# e_BOOK_READER__VERSIUNE_10_v31_FIXED.net
KiCad netlist of a schematic drawn in EAGLE
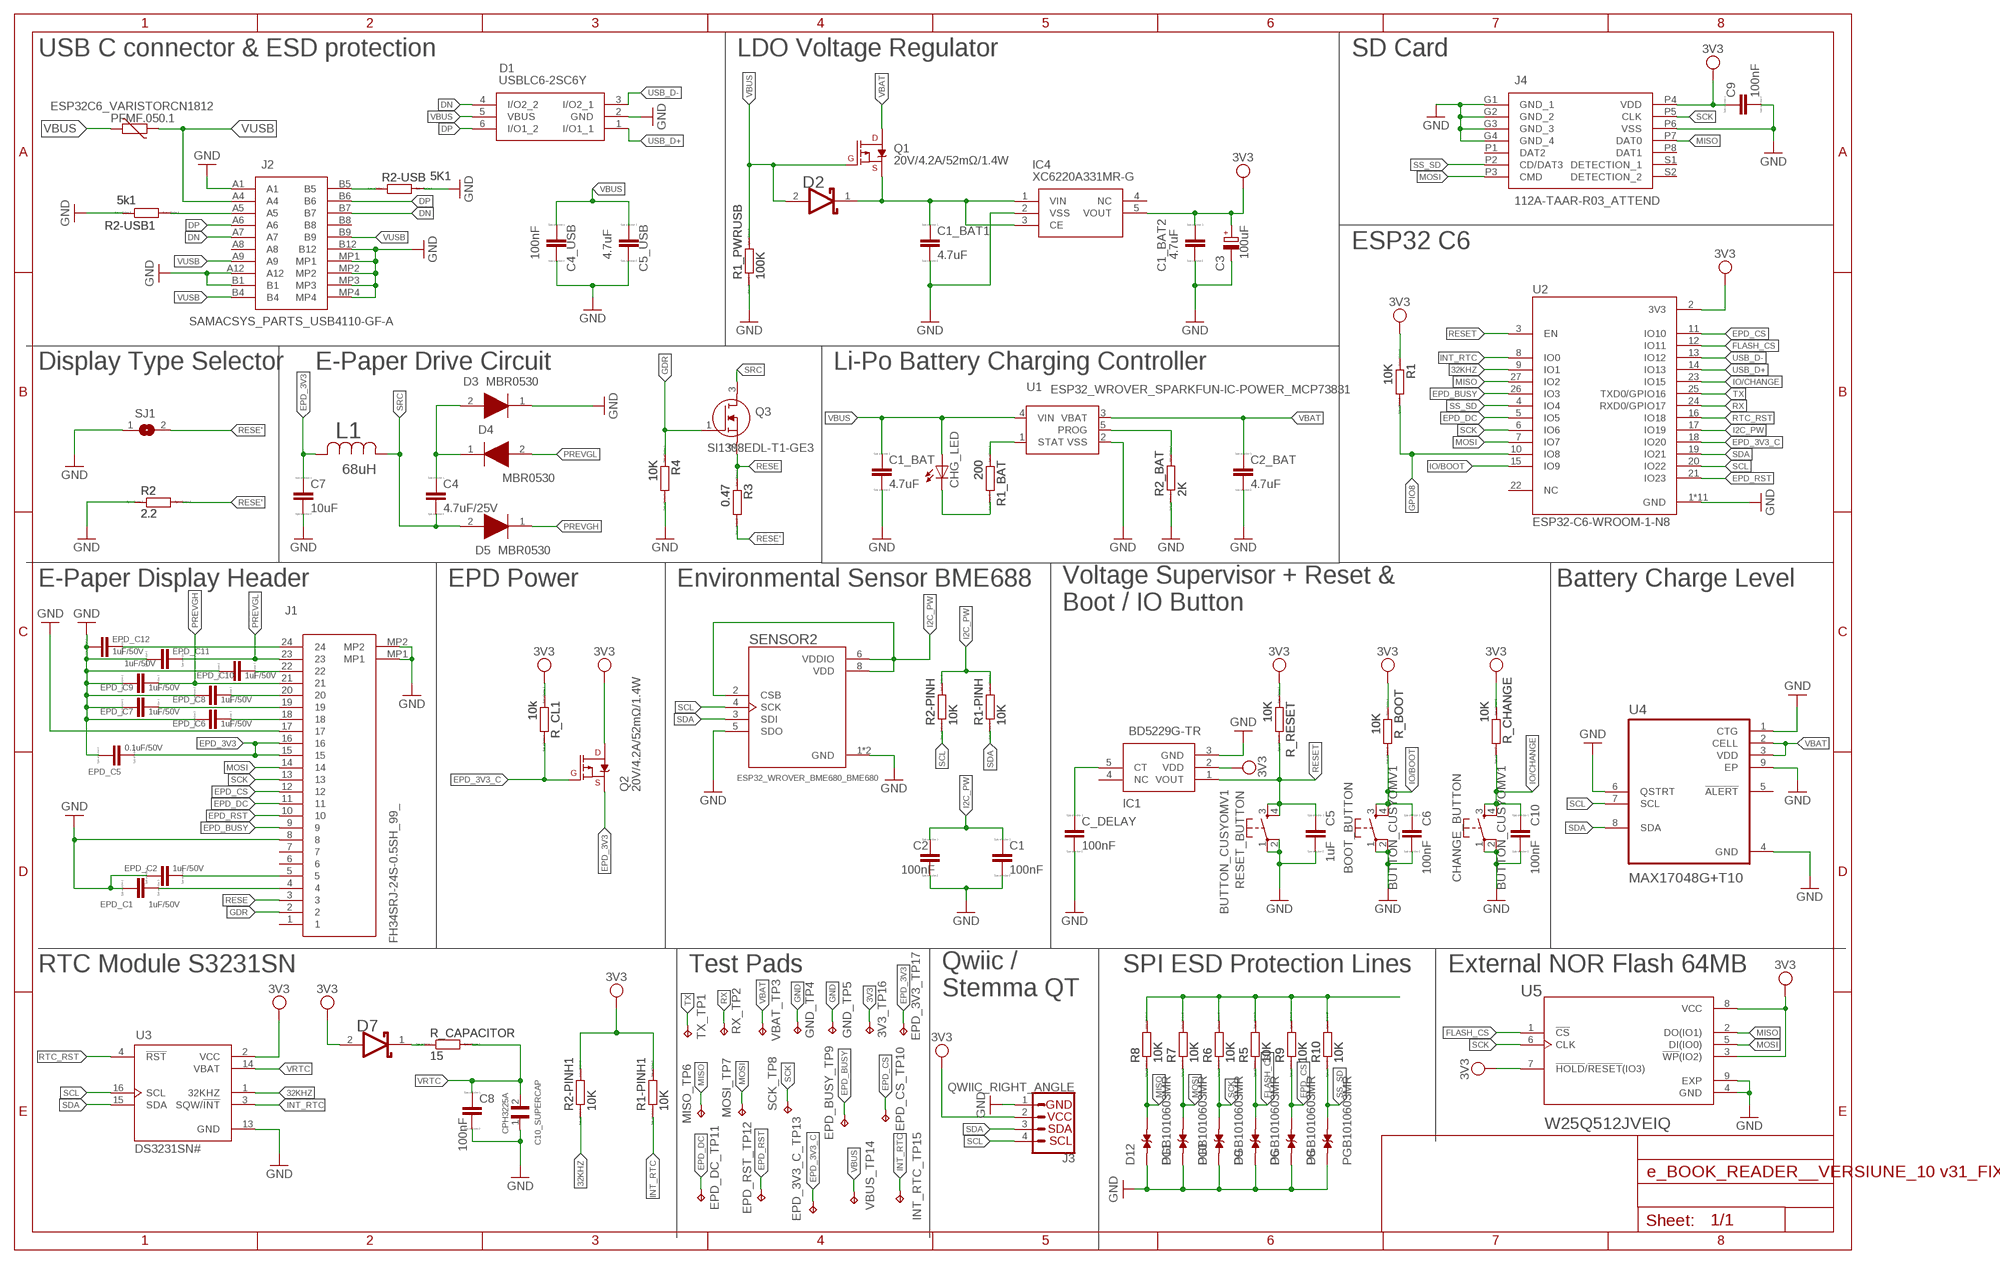
[diagram p0: schematic, sheet 1]

(export (version "E")
  (design (tool "Eeschema 10.0.6"))
  (components
    (comp (ref "3V3_TP16")
      (value "TPTP20R")
      (footprint "eagle-import:TP20R")
      (libsource (lib "eagle-import") (part "TPTP20R"))
    )
    (comp (ref "BOOT_BUTTON")
      (value "BUTTON_CUSYOMV1")
      (footprint "eagle-import:MYBUTTON")
      (libsource (lib "eagle-import") (part "BUTTON_CUSYOMV1"))
    )
    (comp (ref "C1")
      (value "100nF")
      (footprint "eagle-import:ESP32_WROVER_EAGLE-LTSPICE_C0402")
      (libsource (lib "eagle-import") (part "ESP32_WROVER_EAGLE-LTSPICE_CC0402"))
    )
    (comp (ref "C1_BAT")
      (value "4.7uF")
      (footprint "eagle-import:ESP32_WROVER_EAGLE-LTSPICE_C0402")
      (libsource (lib "eagle-import") (part "ESP32_WROVER_EAGLE-LTSPICE_CC0402"))
    )
    (comp (ref "C1_BAT1")
      (value "4.7uF")
      (footprint "eagle-import:ESP32_WROVER_EAGLE-LTSPICE_C0402")
      (libsource (lib "eagle-import") (part "ESP32_WROVER_EAGLE-LTSPICE_CC0402"))
    )
    (comp (ref "C1_BAT2")
      (value "4.7uF")
      (footprint "eagle-import:ESP32_WROVER_EAGLE-LTSPICE_C0402")
      (libsource (lib "eagle-import") (part "ESP32_WROVER_EAGLE-LTSPICE_CC0402"))
    )
    (comp (ref "C2")
      (value "100nF")
      (footprint "eagle-import:ESP32_WROVER_EAGLE-LTSPICE_C0402")
      (libsource (lib "eagle-import") (part "ESP32_WROVER_EAGLE-LTSPICE_CC0402"))
    )
    (comp (ref "C2_BAT")
      (value "4.7uF")
      (footprint "eagle-import:ESP32_WROVER_EAGLE-LTSPICE_C0402")
      (libsource (lib "eagle-import") (part "ESP32_WROVER_EAGLE-LTSPICE_CC0402"))
    )
    (comp (ref "C3")
      (value "100uF")
      (footprint "eagle-import:RCL_CT3528")
      (libsource (lib "eagle-import") (part "RCL_CPOL-EUCT3528"))
    )
    (comp (ref "C4")
      (value "4.7uF/25V")
      (footprint "eagle-import:ESP32_WROVER_EAGLE-LTSPICE_C0402")
      (libsource (lib "eagle-import") (part "ESP32_WROVER_EAGLE-LTSPICE_CC0402"))
    )
    (comp (ref "C4_USB")
      (value "100nF")
      (footprint "eagle-import:ESP32_WROVER_EAGLE-LTSPICE_C0402")
      (libsource (lib "eagle-import") (part "ESP32_WROVER_EAGLE-LTSPICE_CC0402"))
    )
    (comp (ref "C5")
      (value "1uF")
      (footprint "eagle-import:ESP32_WROVER_EAGLE-LTSPICE_C0402")
      (libsource (lib "eagle-import") (part "ESP32_WROVER_EAGLE-LTSPICE_CC0402"))
    )
    (comp (ref "C5_USB")
      (value "4.7uF")
      (footprint "eagle-import:ESP32_WROVER_EAGLE-LTSPICE_C0402")
      (libsource (lib "eagle-import") (part "ESP32_WROVER_EAGLE-LTSPICE_CC0402"))
    )
    (comp (ref "C6")
      (value "100nF")
      (footprint "eagle-import:ESP32_WROVER_EAGLE-LTSPICE_C0402")
      (libsource (lib "eagle-import") (part "ESP32_WROVER_EAGLE-LTSPICE_CC0402"))
    )
    (comp (ref "C7")
      (value "10uF")
      (footprint "eagle-import:ESP32_WROVER_EAGLE-LTSPICE_C0402")
      (libsource (lib "eagle-import") (part "ESP32_WROVER_EAGLE-LTSPICE_CC0402"))
    )
    (comp (ref "C8")
      (value "100nF")
      (footprint "eagle-import:ESP32_WROVER_EAGLE-LTSPICE_C0402")
      (libsource (lib "eagle-import") (part "ESP32_WROVER_EAGLE-LTSPICE_CC0402"))
    )
    (comp (ref "C9")
      (value "100nF")
      (footprint "eagle-import:ESP32_WROVER_EAGLE-LTSPICE_C0402")
      (libsource (lib "eagle-import") (part "ESP32_WROVER_EAGLE-LTSPICE_CC0402"))
    )
    (comp (ref "C10")
      (value "100nF")
      (footprint "eagle-import:ESP32_WROVER_EAGLE-LTSPICE_C0402")
      (libsource (lib "eagle-import") (part "ESP32_WROVER_EAGLE-LTSPICE_CC0402"))
    )
    (comp (ref "C10_SUPERCAP")
      (value "CPH3225A")
      (footprint "eagle-import:CAPCP3225X100N")
      (fields (field (name "MF") "Seiko Instruments"))
      (libsource (lib "eagle-import") (part "CPH3225A"))
    )
    (comp (ref "CHANGE_BUTTON")
      (value "BUTTON_CUSYOMV1")
      (footprint "eagle-import:MYBUTTON")
      (libsource (lib "eagle-import") (part "BUTTON_CUSYOMV1"))
    )
    (comp (ref "CHG_LED")
      (value "ADAFRUIT_LEDCHIP-LED0603")
      (footprint "eagle-import:ADAFRUIT_CHIP-LED0603")
      (libsource (lib "eagle-import") (part "ADAFRUIT_LEDCHIP-LED0603"))
    )
    (comp (ref "C_DELAY")
      (value "100nF")
      (footprint "eagle-import:ESP32_WROVER_EAGLE-LTSPICE_C0402")
      (libsource (lib "eagle-import") (part "ESP32_WROVER_EAGLE-LTSPICE_CC0402"))
    )
    (comp (ref "D1")
      (value "USBLC6-2SC6Y")
      (footprint "eagle-import:SOT95P280X145-6N")
      (fields (field (name "MF") "STMicroelectronics"))
      (libsource (lib "eagle-import") (part "USBLC6-2SC6Y"))
    )
    (comp (ref "D2")
      (value "ESP32_WROVER_AVX---SD0805S020S1R0_AVX_SD0805S020S1R0_0_0AVX_SD0805S020S1R0_0_0")
      (footprint "eagle-import:ESP32_WROVER_AVX---SD0805S020S1R0_AVX_SD0805S020S1R0_0")
      (fields
        (field (name "DIGIKEY_PART_NUMBER") "478-7800-1-ND")
        (field (name "MF") "AVX")
        (field (name "MOUSER_PART_NUMBER") "581-SD0805S020S1R0")
      )
      (libsource (lib "eagle-import") (part "ESP32_WROVER_AVX---SD0805S020S1R0_AVX_SD0805S020S1R0_0_0AVX_SD0805S020S1R0_0_0"))
    )
    (comp (ref "D3")
      (value "MBR0530")
      (footprint "eagle-import:ESP32_WROVER_AVX---SD0805S020S1R0_AVX_SD0805S020S1R0_0")
      (fields (field (name "MF") "ON Semiconductor"))
      (libsource (lib "eagle-import") (part "MBR0530"))
    )
    (comp (ref "D4")
      (value "MBR0530")
      (footprint "eagle-import:ESP32_WROVER_AVX---SD0805S020S1R0_AVX_SD0805S020S1R0_0")
      (fields (field (name "MF") "ON Semiconductor"))
      (libsource (lib "eagle-import") (part "MBR0530"))
    )
    (comp (ref "D5")
      (value "MBR0530")
      (footprint "eagle-import:ESP32_WROVER_AVX---SD0805S020S1R0_AVX_SD0805S020S1R0_0")
      (fields (field (name "MF") "ON Semiconductor"))
      (libsource (lib "eagle-import") (part "MBR0530"))
    )
    (comp (ref "D6")
      (value "PGB1010603MR")
      (footprint "eagle-import:DIOC1608X36N")
      (fields (field (name "MF") "Littelfuse Inc."))
      (libsource (lib "eagle-import") (part "PGB1010603MR"))
    )
    (comp (ref "D7")
      (value "ESP32_WROVER_AVX---SD0805S020S1R0_AVX_SD0805S020S1R0_0_0AVX_SD0805S020S1R0_0_0")
      (footprint "eagle-import:ESP32_WROVER_AVX---SD0805S020S1R0_AVX_SD0805S020S1R0_0")
      (fields
        (field (name "DIGIKEY_PART_NUMBER") "478-7800-1-ND")
        (field (name "MF") "AVX")
        (field (name "MOUSER_PART_NUMBER") "581-SD0805S020S1R0")
      )
      (libsource (lib "eagle-import") (part "ESP32_WROVER_AVX---SD0805S020S1R0_AVX_SD0805S020S1R0_0_0AVX_SD0805S020S1R0_0_0"))
    )
    (comp (ref "D8")
      (value "PGB1010603MR")
      (footprint "eagle-import:DIOC1608X36N")
      (fields (field (name "MF") "Littelfuse Inc."))
      (libsource (lib "eagle-import") (part "PGB1010603MR"))
    )
    (comp (ref "D9")
      (value "PGB1010603MR")
      (footprint "eagle-import:DIOC1608X36N")
      (fields (field (name "MF") "Littelfuse Inc."))
      (libsource (lib "eagle-import") (part "PGB1010603MR"))
    )
    (comp (ref "D10")
      (value "PGB1010603MR")
      (footprint "eagle-import:DIOC1608X36N")
      (fields (field (name "MF") "Littelfuse Inc."))
      (libsource (lib "eagle-import") (part "PGB1010603MR"))
    )
    (comp (ref "D11")
      (value "PGB1010603MR")
      (footprint "eagle-import:DIOC1608X36N")
      (fields (field (name "MF") "Littelfuse Inc."))
      (libsource (lib "eagle-import") (part "PGB1010603MR"))
    )
    (comp (ref "D12")
      (value "PGB1010603MR")
      (footprint "eagle-import:DIOC1608X36N")
      (fields (field (name "MF") "Littelfuse Inc."))
      (libsource (lib "eagle-import") (part "PGB1010603MR"))
    )
    (comp (ref "EPD_3V3_C_TP13")
      (value "TPTP20R")
      (footprint "eagle-import:TP20R")
      (libsource (lib "eagle-import") (part "TPTP20R"))
    )
    (comp (ref "EPD_3V3_TP17")
      (value "TPTP20R")
      (footprint "eagle-import:TP20R")
      (libsource (lib "eagle-import") (part "TPTP20R"))
    )
    (comp (ref "EPD_BUSY_TP9")
      (value "TPTP20R")
      (footprint "eagle-import:TP20R")
      (libsource (lib "eagle-import") (part "TPTP20R"))
    )
    (comp (ref "EPD_C1")
      (value "1uF/50V")
      (footprint "eagle-import:ESP32_WROVER_EAGLE-LTSPICE_C0402")
      (libsource (lib "eagle-import") (part "ESP32_WROVER_EAGLE-LTSPICE_CC0402"))
    )
    (comp (ref "EPD_C2")
      (value "1uF/50V")
      (footprint "eagle-import:ESP32_WROVER_EAGLE-LTSPICE_C0402")
      (libsource (lib "eagle-import") (part "ESP32_WROVER_EAGLE-LTSPICE_CC0402"))
    )
    (comp (ref "EPD_C5")
      (value "0.1uF/50V")
      (footprint "eagle-import:ESP32_WROVER_EAGLE-LTSPICE_C0402")
      (libsource (lib "eagle-import") (part "ESP32_WROVER_EAGLE-LTSPICE_CC0402"))
    )
    (comp (ref "EPD_C6")
      (value "1uF/50V")
      (footprint "eagle-import:ESP32_WROVER_EAGLE-LTSPICE_C0402")
      (libsource (lib "eagle-import") (part "ESP32_WROVER_EAGLE-LTSPICE_CC0402"))
    )
    (comp (ref "EPD_C7")
      (value "1uF/50V")
      (footprint "eagle-import:ESP32_WROVER_EAGLE-LTSPICE_C0402")
      (libsource (lib "eagle-import") (part "ESP32_WROVER_EAGLE-LTSPICE_CC0402"))
    )
    (comp (ref "EPD_C8")
      (value "1uF/50V")
      (footprint "eagle-import:ESP32_WROVER_EAGLE-LTSPICE_C0402")
      (libsource (lib "eagle-import") (part "ESP32_WROVER_EAGLE-LTSPICE_CC0402"))
    )
    (comp (ref "EPD_C9")
      (value "1uF/50V")
      (footprint "eagle-import:ESP32_WROVER_EAGLE-LTSPICE_C0402")
      (libsource (lib "eagle-import") (part "ESP32_WROVER_EAGLE-LTSPICE_CC0402"))
    )
    (comp (ref "EPD_C10")
      (value "1uF/50V")
      (footprint "eagle-import:ESP32_WROVER_EAGLE-LTSPICE_C0402")
      (libsource (lib "eagle-import") (part "ESP32_WROVER_EAGLE-LTSPICE_CC0402"))
    )
    (comp (ref "EPD_C11")
      (value "1uF/50V")
      (footprint "eagle-import:ESP32_WROVER_EAGLE-LTSPICE_C0402")
      (libsource (lib "eagle-import") (part "ESP32_WROVER_EAGLE-LTSPICE_CC0402"))
    )
    (comp (ref "EPD_C12")
      (value "1uF/50V")
      (footprint "eagle-import:ESP32_WROVER_EAGLE-LTSPICE_C0402")
      (libsource (lib "eagle-import") (part "ESP32_WROVER_EAGLE-LTSPICE_CC0402"))
    )
    (comp (ref "EPD_CS_TP10")
      (value "TPTP20R")
      (footprint "eagle-import:TP20R")
      (libsource (lib "eagle-import") (part "TPTP20R"))
    )
    (comp (ref "EPD_DC_TP11")
      (value "TPTP20R")
      (footprint "eagle-import:TP20R")
      (libsource (lib "eagle-import") (part "TPTP20R"))
    )
    (comp (ref "EPD_RST_TP12")
      (value "TPTP20R")
      (footprint "eagle-import:TP20R")
      (libsource (lib "eagle-import") (part "TPTP20R"))
    )
    (comp (ref "GND_TP4")
      (value "TPTP20R")
      (footprint "eagle-import:TP20R")
      (libsource (lib "eagle-import") (part "TPTP20R"))
    )
    (comp (ref "GND_TP5")
      (value "TPTP20R")
      (footprint "eagle-import:TP20R")
      (libsource (lib "eagle-import") (part "TPTP20R"))
    )
    (comp (ref "IC1")
      (value "BD5229G-TR")
      (footprint "eagle-import:SOT95P280X125-5N")
      (fields (field (name "MOUSER_PART_NUMBER") "755-BD5229G-TR"))
      (libsource (lib "eagle-import") (part "BD5229G-TR"))
    )
    (comp (ref "IC4")
      (value "XC6220A331MR-G")
      (footprint "eagle-import:SOT95P280X120-5N")
      (fields (field (name "MOUSER_PART_NUMBER") "865-XC6220A331MR-G"))
      (libsource (lib "eagle-import") (part "XC6220A331MR-G"))
    )
    (comp (ref "INT_RTC_TP15")
      (value "TPTP20R")
      (footprint "eagle-import:TP20R")
      (libsource (lib "eagle-import") (part "TPTP20R"))
    )
    (comp (ref "J1")
      (value "FH34SRJ-24S-0.5SH_99_")
      (footprint "eagle-import:FH34SRJ24S05SH99")
      (fields
        (field (name "MANUFACTURER_PART_NUMBER") "FH34SRJ-24S-0.5SH(99)")
        (field (name "MOUSER_PART_NUMBER") "798-FH34SRJ24S05SH99")
      )
      (libsource (lib "eagle-import") (part "FH34SRJ-24S-0.5SH_99_"))
    )
    (comp (ref "J2")
      (value "SAMACSYS_PARTS_USB4110-GF-A")
      (footprint "eagle-import:SAMACSYS_PARTS_USB4110GFA")
      (fields
        (field (name "MANUFACTURER_PART_NUMBER") "USB4110-GF-A")
        (field (name "MOUSER_PART_NUMBER") "640-USB4110-GF-A")
      )
      (libsource (lib "eagle-import") (part "SAMACSYS_PARTS_USB4110-GF-A"))
    )
    (comp (ref "J3")
      (value "QWIIC_RIGHT_ANGLE")
      (footprint "eagle-import:JST04_1MM_RA")
      (libsource (lib "eagle-import") (part "QWIIC_CONNECTORJS-1MM"))
    )
    (comp (ref "J4")
      (value "112A-TAAR-R03_ATTEND")
      (footprint "eagle-import:112ATAARR03ATTEND")
      (fields (field (name "MANUFACTURER_PART_NUMBER") "112A-TAAR-R03 ATTEND"))
      (libsource (lib "eagle-import") (part "112A-TAAR-R03_ATTEND"))
    )
    (comp (ref "L1")
      (value "68uH")
      (footprint "eagle-import:IND_4828-WE-TPC_WRE")
      (fields
        (field (name "MANUFACTURER_PART_NUMBER") "744043680")
        (field (name "COPYRIGHT") "Copyright (C) 2024 Ultra Librarian. All rights reserved.")
      )
      (libsource (lib "eagle-import") (part "744043680IND_4828-WE-TPC_WRE"))
    )
    (comp (ref "MISO_TP6")
      (value "TPTP20R")
      (footprint "eagle-import:TP20R")
      (libsource (lib "eagle-import") (part "TPTP20R"))
    )
    (comp (ref "MOSI_TP7")
      (value "TPTP20R")
      (footprint "eagle-import:TP20R")
      (libsource (lib "eagle-import") (part "TPTP20R"))
    )
    (comp (ref "PFMF.050.1")
      (value "ESP32C6_VARISTORCN1812")
      (footprint "eagle-import:ESP32C6_VARISTOR_CT_CN1812")
      (libsource (lib "eagle-import") (part "ESP32C6_VARISTORCN1812"))
    )
    (comp (ref "Q1")
      (value "20V/4.2A/52mΩ/1.4W")
      (footprint "eagle-import:ESP32_WROVER_SPARKFUN-DISCRETESEMI_SOT23-3")
      (libsource (lib "eagle-import") (part "ESP32_WROVER_SPARKFUN-DISCRETESEMI_MOSFET_PCH-DMG2305UX-7"))
    )
    (comp (ref "Q2")
      (value "20V/4.2A/52mΩ/1.4W")
      (footprint "eagle-import:ESP32_WROVER_SPARKFUN-DISCRETESEMI_SOT23-3")
      (libsource (lib "eagle-import") (part "ESP32_WROVER_SPARKFUN-DISCRETESEMI_MOSFET_PCH-DMG2305UX-7"))
    )
    (comp (ref "Q3")
      (value "SI1308EDL-T1-GE3")
      (footprint "eagle-import:SOT65P210X110-3N")
      (fields (field (name "MF") "Vishay Siliconix"))
      (libsource (lib "eagle-import") (part "SI1308EDL-T1-GE3"))
    )
    (comp (ref "R1")
      (value "10K")
      (footprint "eagle-import:ESP32_WROVER_EAGLE-LTSPICE_R0402")
      (libsource (lib "eagle-import") (part "ESP32_WROVER_EAGLE-LTSPICE_RR0402"))
    )
    (comp (ref "R1-PINH")
      (value "10K")
      (footprint "eagle-import:ESP32_WROVER_EAGLE-LTSPICE_R0402")
      (libsource (lib "eagle-import") (part "ESP32_WROVER_EAGLE-LTSPICE_RR0402"))
    )
    (comp (ref "R1-PINH1")
      (value "10K")
      (footprint "eagle-import:ESP32_WROVER_EAGLE-LTSPICE_R0402")
      (libsource (lib "eagle-import") (part "ESP32_WROVER_EAGLE-LTSPICE_RR0402"))
    )
    (comp (ref "R1_BAT")
      (value "200")
      (footprint "eagle-import:ESP32_WROVER_EAGLE-LTSPICE_R0402")
      (libsource (lib "eagle-import") (part "ESP32_WROVER_EAGLE-LTSPICE_RR0402"))
    )
    (comp (ref "R1_PWRUSB")
      (value "100K")
      (footprint "eagle-import:ESP32_WROVER_EAGLE-LTSPICE_R0402")
      (libsource (lib "eagle-import") (part "ESP32_WROVER_EAGLE-LTSPICE_RR0402"))
    )
    (comp (ref "R2")
      (value "2.2")
      (footprint "eagle-import:ESP32_WROVER_EAGLE-LTSPICE_R0402")
      (libsource (lib "eagle-import") (part "ESP32_WROVER_EAGLE-LTSPICE_RR0402"))
    )
    (comp (ref "R2-PINH")
      (value "10K")
      (footprint "eagle-import:ESP32_WROVER_EAGLE-LTSPICE_R0402")
      (libsource (lib "eagle-import") (part "ESP32_WROVER_EAGLE-LTSPICE_RR0402"))
    )
    (comp (ref "R2-PINH1")
      (value "10K")
      (footprint "eagle-import:ESP32_WROVER_EAGLE-LTSPICE_R0402")
      (libsource (lib "eagle-import") (part "ESP32_WROVER_EAGLE-LTSPICE_RR0402"))
    )
    (comp (ref "R2-USB")
      (value "5K1")
      (footprint "eagle-import:ESP32_WROVER_EAGLE-LTSPICE_R0402")
      (libsource (lib "eagle-import") (part "ESP32_WROVER_EAGLE-LTSPICE_RR0402"))
    )
    (comp (ref "R2-USB1")
      (value "5k1")
      (footprint "eagle-import:ESP32_WROVER_EAGLE-LTSPICE_R0402")
      (libsource (lib "eagle-import") (part "ESP32_WROVER_EAGLE-LTSPICE_RR0402"))
    )
    (comp (ref "R2_BAT")
      (value "2K")
      (footprint "eagle-import:ESP32_WROVER_EAGLE-LTSPICE_R0402")
      (libsource (lib "eagle-import") (part "ESP32_WROVER_EAGLE-LTSPICE_RR0402"))
    )
    (comp (ref "R3")
      (value "0.47")
      (footprint "eagle-import:ESP32_WROVER_EAGLE-LTSPICE_R0402")
      (libsource (lib "eagle-import") (part "ESP32_WROVER_EAGLE-LTSPICE_RR0402"))
    )
    (comp (ref "R4")
      (value "10K")
      (footprint "eagle-import:ESP32_WROVER_EAGLE-LTSPICE_R0402")
      (libsource (lib "eagle-import") (part "ESP32_WROVER_EAGLE-LTSPICE_RR0402"))
    )
    (comp (ref "R5")
      (value "10K")
      (footprint "eagle-import:ESP32_WROVER_EAGLE-LTSPICE_R0402")
      (libsource (lib "eagle-import") (part "ESP32_WROVER_EAGLE-LTSPICE_RR0402"))
    )
    (comp (ref "R6")
      (value "10K")
      (footprint "eagle-import:ESP32_WROVER_EAGLE-LTSPICE_R0402")
      (libsource (lib "eagle-import") (part "ESP32_WROVER_EAGLE-LTSPICE_RR0402"))
    )
    (comp (ref "R7")
      (value "10K")
      (footprint "eagle-import:ESP32_WROVER_EAGLE-LTSPICE_R0402")
      (libsource (lib "eagle-import") (part "ESP32_WROVER_EAGLE-LTSPICE_RR0402"))
    )
    (comp (ref "R8")
      (value "10K")
      (footprint "eagle-import:ESP32_WROVER_EAGLE-LTSPICE_R0402")
      (libsource (lib "eagle-import") (part "ESP32_WROVER_EAGLE-LTSPICE_RR0402"))
    )
    (comp (ref "R9")
      (value "10K")
      (footprint "eagle-import:ESP32_WROVER_EAGLE-LTSPICE_R0402")
      (libsource (lib "eagle-import") (part "ESP32_WROVER_EAGLE-LTSPICE_RR0402"))
    )
    (comp (ref "R10")
      (value "10K")
      (footprint "eagle-import:ESP32_WROVER_EAGLE-LTSPICE_R0402")
      (libsource (lib "eagle-import") (part "ESP32_WROVER_EAGLE-LTSPICE_RR0402"))
    )
    (comp (ref "RESET_BUTTON")
      (value "BUTTON_CUSYOMV1")
      (footprint "eagle-import:MYBUTTON")
      (libsource (lib "eagle-import") (part "BUTTON_CUSYOMV1"))
    )
    (comp (ref "RX_TP2")
      (value "TPTP20R")
      (footprint "eagle-import:TP20R")
      (libsource (lib "eagle-import") (part "TPTP20R"))
    )
    (comp (ref "R_BOOT")
      (value "10K")
      (footprint "eagle-import:ESP32_WROVER_EAGLE-LTSPICE_R0402")
      (libsource (lib "eagle-import") (part "ESP32_WROVER_EAGLE-LTSPICE_RR0402"))
    )
    (comp (ref "R_CAPACITOR")
      (value "15")
      (footprint "eagle-import:ESP32_WROVER_EAGLE-LTSPICE_R0402")
      (libsource (lib "eagle-import") (part "ESP32_WROVER_EAGLE-LTSPICE_RR0402"))
    )
    (comp (ref "R_CHANGE")
      (value "10K")
      (footprint "eagle-import:ESP32_WROVER_EAGLE-LTSPICE_R0402")
      (libsource (lib "eagle-import") (part "ESP32_WROVER_EAGLE-LTSPICE_RR0402"))
    )
    (comp (ref "R_CL1")
      (value "10k")
      (footprint "eagle-import:ESP32_WROVER_EAGLE-LTSPICE_R0402")
      (libsource (lib "eagle-import") (part "ESP32_WROVER_EAGLE-LTSPICE_RR0402"))
    )
    (comp (ref "R_RESET")
      (value "10K")
      (footprint "eagle-import:ESP32_WROVER_EAGLE-LTSPICE_R0402")
      (libsource (lib "eagle-import") (part "ESP32_WROVER_EAGLE-LTSPICE_RR0402"))
    )
    (comp (ref "SCK_TP8")
      (value "TPTP20R")
      (footprint "eagle-import:TP20R")
      (libsource (lib "eagle-import") (part "TPTP20R"))
    )
    (comp (ref "SENSOR2")
      (value "ESP32_WROVER_BME680_BME680")
      (footprint "eagle-import:ESP32_WROVER_BME680_PSON80P300X300X100-8N")
      (fields (field (name "MF") "Bosch Sensortec") (field (name "MP") "BME680"))
      (libsource (lib "eagle-import") (part "ESP32_WROVER_BME680_BME680"))
    )
    (comp (ref "SJ1") (value "SJ") (footprint "eagle-import:SJ") (libsource (lib "eagle-import") (part "SJ")))
    (comp (ref "TX_TP1")
      (value "TPTP20R")
      (footprint "eagle-import:TP20R")
      (libsource (lib "eagle-import") (part "TPTP20R"))
    )
    (comp (ref "U1")
      (value "ESP32_WROVER_SPARKFUN-IC-POWER_MCP73831")
      (footprint "eagle-import:ESP32_WROVER_SPARKFUN-IC-POWER_SOT23-5")
      (libsource (lib "eagle-import") (part "ESP32_WROVER_SPARKFUN-IC-POWER_MCP73831"))
    )
    (comp (ref "U2")
      (value "ESP32-C6-WROOM-1-N8")
      (footprint "eagle-import:XCVR_ESP32-C6-WROOM-1-N8")
      (fields (field (name "MF") "Espressif Systems"))
      (libsource (lib "eagle-import") (part "ESP32-C6-WROOM-1-N8"))
    )
    (comp (ref "U3")
      (value "DS3231SN#")
      (footprint "eagle-import:SOIC127P1032X265-16N")
      (fields (field (name "MF") "Analog Devices"))
      (libsource (lib "eagle-import") (part "DS3231SN#"))
    )
    (comp (ref "U4")
      (value "MAX17048G+T10")
      (footprint "eagle-import:SON50P200X200X80-9N")
      (fields (field (name "MF") "Analog Devices"))
      (libsource (lib "eagle-import") (part "MAX17048G+T10"))
    )
    (comp (ref "U5")
      (value "W25Q512JVEIQ")
      (footprint "eagle-import:SON127P600X800X80-9N")
      (fields (field (name "MF") "Winbond Electronics"))
      (libsource (lib "eagle-import") (part "W25Q512JVEIQ"))
    )
    (comp (ref "VBAT_TP3")
      (value "TPTP20R")
      (footprint "eagle-import:TP20R")
      (libsource (lib "eagle-import") (part "TPTP20R"))
    )
    (comp (ref "VBUS_TP14")
      (value "TPTP20R")
      (footprint "eagle-import:TP20R")
      (libsource (lib "eagle-import") (part "TPTP20R"))
    )
  )
  (nets
    (net (code "1") (name "3V3") (class "Default")
      (node (ref "3V3_TP16") (pin "TP") (pinfunction "TP_TP") (pintype "input"))
      (node (ref "C1_BAT2") (pin "1") (pinfunction "1_1") (pintype "passive"))
      (node (ref "C3") (pin "+") (pinfunction "+_+") (pintype "passive"))
      (node (ref "C9") (pin "1") (pinfunction "1_1") (pintype "passive"))
      (node (ref "D7") (pin "2") (pinfunction "ANODE_2") (pintype "bidirectional"))
      (node (ref "IC1") (pin "2") (pinfunction "VDD_2") (pintype "bidirectional"))
      (node (ref "IC4") (pin "5") (pinfunction "VOUT_5") (pintype "bidirectional"))
      (node (ref "J3") (pin "2") (pinfunction "2_2") (pintype "power_in"))
      (node (ref "J4") (pin "P4") (pinfunction "VDD_P4") (pintype "bidirectional"))
      (node (ref "Q2") (pin "3") (pinfunction "D_3") (pintype "bidirectional"))
      (node (ref "R1") (pin "1") (pinfunction "1_1") (pintype "passive"))
      (node (ref "R1-PINH1") (pin "2") (pinfunction "2_2") (pintype "passive"))
      (node (ref "R2-PINH1") (pin "2") (pinfunction "2_2") (pintype "passive"))
      (node (ref "R_BOOT") (pin "1") (pinfunction "1_1") (pintype "passive"))
      (node (ref "R_CHANGE") (pin "1") (pinfunction "1_1") (pintype "passive"))
      (node (ref "R_CL1") (pin "1") (pinfunction "1_1") (pintype "passive"))
      (node (ref "R_RESET") (pin "1") (pinfunction "1_1") (pintype "passive"))
      (node (ref "U2") (pin "2") (pinfunction "3V3_2") (pintype "power_in"))
      (node (ref "U3") (pin "2") (pinfunction "VCC_2") (pintype "power_in"))
      (node (ref "U5") (pin "3") (pinfunction "~{WP}(IO2)_3") (pintype "bidirectional"))
      (node (ref "U5") (pin "7") (pinfunction "~{HOLD}/~{RESET}(IO3)_7") (pintype "bidirectional"))
      (node (ref "U5") (pin "8") (pinfunction "VCC_8") (pintype "power_in"))
    )
    (net (code "2") (name "32KHZ") (class "Default")
      (node (ref "R2-PINH1") (pin "1") (pinfunction "1_1") (pintype "passive"))
      (node (ref "U2") (pin "9") (pinfunction "IO1_9") (pintype "bidirectional"))
      (node (ref "U3") (pin "1") (pinfunction "32KHZ_1") (pintype "output"))
    )
    (net (code "3") (name "DN") (class "Default")
      (node (ref "D1") (pin "4") (pinfunction "I/O2_2_4") (pintype "bidirectional"))
      (node (ref "J2") (pin "A7") (pinfunction "A7_A7") (pintype "bidirectional"))
      (node (ref "J2") (pin "B7") (pinfunction "B7_B7") (pintype "bidirectional"))
    )
    (net (code "4") (name "DP") (class "Default")
      (node (ref "D1") (pin "6") (pinfunction "I/O1_2_6") (pintype "bidirectional"))
      (node (ref "J2") (pin "A6") (pinfunction "A6_A6") (pintype "bidirectional"))
      (node (ref "J2") (pin "B6") (pinfunction "B6_B6") (pintype "bidirectional"))
    )
    (net (code "5") (name "EPD_3V3") (class "Default")
      (node (ref "C7") (pin "1") (pinfunction "1_1") (pintype "passive"))
      (node (ref "EPD_3V3_TP17") (pin "TP") (pinfunction "TP_TP") (pintype "input"))
      (node (ref "EPD_C5") (pin "1") (pinfunction "1_1") (pintype "passive"))
      (node (ref "J1") (pin "15") (pinfunction "15_15") (pintype "bidirectional"))
      (node (ref "J1") (pin "16") (pinfunction "16_16") (pintype "bidirectional"))
      (node (ref "L1") (pin "2") (pinfunction "2_2") (pintype "passive"))
      (node (ref "Q2") (pin "2") (pinfunction "S_2") (pintype "bidirectional"))
    )
    (net (code "6") (name "EPD_3V3_C") (class "Default")
      (node (ref "EPD_3V3_C_TP13") (pin "TP") (pinfunction "TP_TP") (pintype "input"))
      (node (ref "Q2") (pin "1") (pinfunction "G_1") (pintype "bidirectional"))
      (node (ref "R_CL1") (pin "2") (pinfunction "2_2") (pintype "passive"))
      (node (ref "U2") (pin "18") (pinfunction "IO20_18") (pintype "bidirectional"))
    )
    (net (code "7") (name "EPD_BUSY") (class "Default")
      (node (ref "EPD_BUSY_TP9") (pin "TP") (pinfunction "TP_TP") (pintype "input"))
      (node (ref "J1") (pin "9") (pinfunction "9_9") (pintype "bidirectional"))
      (node (ref "U2") (pin "26") (pinfunction "IO3_26") (pintype "bidirectional"))
    )
    (net (code "8") (name "EPD_CS") (class "Default")
      (node (ref "D6") (pin "2") (pinfunction "2_2") (pintype "passive"))
      (node (ref "EPD_CS_TP10") (pin "TP") (pinfunction "TP_TP") (pintype "input"))
      (node (ref "J1") (pin "12") (pinfunction "12_12") (pintype "bidirectional"))
      (node (ref "R9") (pin "1") (pinfunction "1_1") (pintype "passive"))
      (node (ref "U2") (pin "11") (pinfunction "IO10_11") (pintype "bidirectional"))
    )
    (net (code "9") (name "EPD_DC") (class "Default")
      (node (ref "EPD_DC_TP11") (pin "TP") (pinfunction "TP_TP") (pintype "input"))
      (node (ref "J1") (pin "11") (pinfunction "11_11") (pintype "bidirectional"))
      (node (ref "U2") (pin "5") (pinfunction "IO5_5") (pintype "bidirectional"))
    )
    (net (code "10") (name "EPD_RST") (class "Default")
      (node (ref "EPD_RST_TP12") (pin "TP") (pinfunction "TP_TP") (pintype "input"))
      (node (ref "J1") (pin "10") (pinfunction "10_10") (pintype "bidirectional"))
      (node (ref "U2") (pin "21") (pinfunction "IO23_21") (pintype "bidirectional"))
    )
    (net (code "11") (name "FLASH_CS") (class "Default")
      (node (ref "D9") (pin "2") (pinfunction "2_2") (pintype "passive"))
      (node (ref "R5") (pin "1") (pinfunction "1_1") (pintype "passive"))
      (node (ref "U2") (pin "12") (pinfunction "IO11_12") (pintype "bidirectional"))
      (node (ref "U5") (pin "1") (pinfunction "~{CS}_1") (pintype "input"))
    )
    (net (code "12") (name "GDR") (class "Default")
      (node (ref "J1") (pin "2") (pinfunction "2_2") (pintype "bidirectional"))
      (node (ref "Q3") (pin "1") (pinfunction "G_1") (pintype "bidirectional"))
      (node (ref "R4") (pin "1") (pinfunction "1_1") (pintype "passive"))
    )
    (net (code "13") (name "GND") (class "Default")
      (node (ref "BOOT_BUTTON") (pin "1") (pinfunction "1_1") (pintype "passive"))
      (node (ref "BOOT_BUTTON") (pin "2") (pinfunction "2_2") (pintype "passive"))
      (node (ref "C1") (pin "2") (pinfunction "2_2") (pintype "passive"))
      (node (ref "C10") (pin "2") (pinfunction "2_2") (pintype "passive"))
      (node (ref "C10_SUPERCAP") (pin "1") (pinfunction "1_1") (pintype "passive"))
      (node (ref "C1_BAT") (pin "2") (pinfunction "2_2") (pintype "passive"))
      (node (ref "C1_BAT1") (pin "2") (pinfunction "2_2") (pintype "passive"))
      (node (ref "C1_BAT2") (pin "2") (pinfunction "2_2") (pintype "passive"))
      (node (ref "C2") (pin "2") (pinfunction "2_2") (pintype "passive"))
      (node (ref "C2_BAT") (pin "2") (pinfunction "2_2") (pintype "passive"))
      (node (ref "C3") (pin "-") (pinfunction "-_-") (pintype "passive"))
      (node (ref "C4_USB") (pin "2") (pinfunction "2_2") (pintype "passive"))
      (node (ref "C5") (pin "2") (pinfunction "2_2") (pintype "passive"))
      (node (ref "C5_USB") (pin "2") (pinfunction "2_2") (pintype "passive"))
      (node (ref "C6") (pin "2") (pinfunction "2_2") (pintype "passive"))
      (node (ref "C7") (pin "2") (pinfunction "2_2") (pintype "passive"))
      (node (ref "C8") (pin "2") (pinfunction "2_2") (pintype "passive"))
      (node (ref "C9") (pin "2") (pinfunction "2_2") (pintype "passive"))
      (node (ref "CHANGE_BUTTON") (pin "1") (pinfunction "1_1") (pintype "passive"))
      (node (ref "CHANGE_BUTTON") (pin "2") (pinfunction "2_2") (pintype "passive"))
      (node (ref "C_DELAY") (pin "2") (pinfunction "2_2") (pintype "passive"))
      (node (ref "D1") (pin "2") (pinfunction "GND_2") (pintype "bidirectional"))
      (node (ref "D10") (pin "1") (pinfunction "1_1") (pintype "passive"))
      (node (ref "D11") (pin "1") (pinfunction "1_1") (pintype "passive"))
      (node (ref "D12") (pin "1") (pinfunction "1_1") (pintype "passive"))
      (node (ref "D3") (pin "1") (pinfunction "K_1") (pintype "bidirectional"))
      (node (ref "D6") (pin "1") (pinfunction "1_1") (pintype "passive"))
      (node (ref "D8") (pin "1") (pinfunction "1_1") (pintype "passive"))
      (node (ref "D9") (pin "1") (pinfunction "1_1") (pintype "passive"))
      (node (ref "EPD_C1") (pin "2") (pinfunction "2_2") (pintype "passive"))
      (node (ref "EPD_C10") (pin "2") (pinfunction "2_2") (pintype "passive"))
      (node (ref "EPD_C11") (pin "2") (pinfunction "2_2") (pintype "passive"))
      (node (ref "EPD_C12") (pin "2") (pinfunction "2_2") (pintype "passive"))
      (node (ref "EPD_C2") (pin "2") (pinfunction "2_2") (pintype "passive"))
      (node (ref "EPD_C5") (pin "2") (pinfunction "2_2") (pintype "passive"))
      (node (ref "EPD_C6") (pin "2") (pinfunction "2_2") (pintype "passive"))
      (node (ref "EPD_C7") (pin "2") (pinfunction "2_2") (pintype "passive"))
      (node (ref "EPD_C8") (pin "2") (pinfunction "2_2") (pintype "passive"))
      (node (ref "EPD_C9") (pin "2") (pinfunction "2_2") (pintype "passive"))
      (node (ref "GND_TP4") (pin "TP") (pinfunction "TP_TP") (pintype "input"))
      (node (ref "GND_TP5") (pin "TP") (pinfunction "TP_TP") (pintype "input"))
      (node (ref "IC1") (pin "3") (pinfunction "GND_3") (pintype "bidirectional"))
      (node (ref "IC4") (pin "2") (pinfunction "VSS_2") (pintype "bidirectional"))
      (node (ref "J1") (pin "17") (pinfunction "17_17") (pintype "bidirectional"))
      (node (ref "J1") (pin "8") (pinfunction "8_8") (pintype "bidirectional"))
      (node (ref "J1") (pin "MP1") (pinfunction "MP1_MP1") (pintype "bidirectional"))
      (node (ref "J1") (pin "MP2") (pinfunction "MP2_MP2") (pintype "bidirectional"))
      (node (ref "J2") (pin "A1") (pinfunction "A1_A1") (pintype "bidirectional"))
      (node (ref "J2") (pin "A12") (pinfunction "A12_A12") (pintype "bidirectional"))
      (node (ref "J2") (pin "B1") (pinfunction "B1_B1") (pintype "bidirectional"))
      (node (ref "J2") (pin "B12") (pinfunction "B12_B12") (pintype "bidirectional"))
      (node (ref "J2") (pin "MP1") (pinfunction "MP1_MP1") (pintype "bidirectional"))
      (node (ref "J2") (pin "MP2") (pinfunction "MP2_MP2") (pintype "bidirectional"))
      (node (ref "J2") (pin "MP3") (pinfunction "MP3_MP3") (pintype "bidirectional"))
      (node (ref "J2") (pin "MP4") (pinfunction "MP4_MP4") (pintype "bidirectional"))
      (node (ref "J3") (pin "1") (pinfunction "1_1") (pintype "power_in"))
      (node (ref "J4") (pin "G1") (pinfunction "GND_1_G1") (pintype "bidirectional"))
      (node (ref "J4") (pin "G2") (pinfunction "GND_2_G2") (pintype "bidirectional"))
      (node (ref "J4") (pin "G3") (pinfunction "GND_3_G3") (pintype "bidirectional"))
      (node (ref "J4") (pin "G4") (pinfunction "GND_4_G4") (pintype "bidirectional"))
      (node (ref "J4") (pin "P6") (pinfunction "VSS_P6") (pintype "bidirectional"))
      (node (ref "R1_PWRUSB") (pin "1") (pinfunction "1_1") (pintype "passive"))
      (node (ref "R2") (pin "1") (pinfunction "1_1") (pintype "passive"))
      (node (ref "R2-USB") (pin "2") (pinfunction "2_2") (pintype "passive"))
      (node (ref "R2-USB1") (pin "1") (pinfunction "1_1") (pintype "passive"))
      (node (ref "R2_BAT") (pin "1") (pinfunction "1_1") (pintype "passive"))
      (node (ref "R4") (pin "2") (pinfunction "2_2") (pintype "passive"))
      (node (ref "RESET_BUTTON") (pin "1") (pinfunction "1_1") (pintype "passive"))
      (node (ref "RESET_BUTTON") (pin "2") (pinfunction "2_2") (pintype "passive"))
      (node (ref "SENSOR2") (pin "1") (pinfunction "GND_1") (pintype "power_in"))
      (node (ref "SENSOR2") (pin "5") (pinfunction "SDO_5") (pintype "bidirectional"))
      (node (ref "SENSOR2") (pin "7") (pinfunction "GND_7") (pintype "power_in"))
      (node (ref "SJ1") (pin "1") (pinfunction "1_1") (pintype "passive"))
      (node (ref "U1") (pin "2") (pinfunction "VSS_2") (pintype "power_in"))
      (node (ref "U2") (pin "1") (pinfunction "GND_1") (pintype "power_in"))
      (node (ref "U2") (pin "28") (pinfunction "GND_28") (pintype "power_in"))
      (node (ref "U2") (pin "29_1") (pinfunction "GND_29_1") (pintype "power_in"))
      (node (ref "U2") (pin "29_2") (pinfunction "GND_29_2") (pintype "power_in"))
      (node (ref "U2") (pin "29_3") (pinfunction "GND_29_3") (pintype "power_in"))
      (node (ref "U2") (pin "29_4") (pinfunction "GND_29_4") (pintype "power_in"))
      (node (ref "U2") (pin "29_5") (pinfunction "GND_29_5") (pintype "power_in"))
      (node (ref "U2") (pin "29_6") (pinfunction "GND_29_6") (pintype "power_in"))
      (node (ref "U2") (pin "29_7") (pinfunction "GND_29_7") (pintype "power_in"))
      (node (ref "U2") (pin "29_8") (pinfunction "GND_29_8") (pintype "power_in"))
      (node (ref "U2") (pin "29_9") (pinfunction "GND_29_9") (pintype "power_in"))
      (node (ref "U3") (pin "13") (pinfunction "GND_13") (pintype "power_in"))
      (node (ref "U4") (pin "1") (pinfunction "CTG_1") (pintype "power_in"))
      (node (ref "U4") (pin "4") (pinfunction "GND_4") (pintype "power_in"))
      (node (ref "U4") (pin "6") (pinfunction "QSTRT_6") (pintype "input"))
      (node (ref "U4") (pin "9") (pinfunction "EP_9") (pintype "power_in"))
      (node (ref "U5") (pin "4") (pinfunction "GND_4") (pintype "power_in"))
      (node (ref "U5") (pin "9") (pinfunction "EXP_9") (pintype "passive"))
    )
    (net (code "14") (name "GPIO8") (class "Default")
      (node (ref "R1") (pin "2") (pinfunction "2_2") (pintype "passive"))
      (node (ref "U2") (pin "10") (pinfunction "IO8_10") (pintype "bidirectional"))
    )
    (net (code "15") (name "I2C_PW") (class "Default")
      (node (ref "C1") (pin "1") (pinfunction "1_1") (pintype "passive"))
      (node (ref "C2") (pin "1") (pinfunction "1_1") (pintype "passive"))
      (node (ref "R1-PINH") (pin "2") (pinfunction "2_2") (pintype "passive"))
      (node (ref "R2-PINH") (pin "2") (pinfunction "2_2") (pintype "passive"))
      (node (ref "SENSOR2") (pin "2") (pinfunction "CSB_2") (pintype "input"))
      (node (ref "SENSOR2") (pin "6") (pinfunction "VDDIO_6") (pintype "power_in"))
      (node (ref "SENSOR2") (pin "8") (pinfunction "VDD_8") (pintype "power_in"))
      (node (ref "U2") (pin "17") (pinfunction "IO19_17") (pintype "bidirectional"))
    )
    (net (code "16") (name "INT_RTC") (class "Default")
      (node (ref "INT_RTC_TP15") (pin "TP") (pinfunction "TP_TP") (pintype "input"))
      (node (ref "R1-PINH1") (pin "1") (pinfunction "1_1") (pintype "passive"))
      (node (ref "U2") (pin "8") (pinfunction "IO0_8") (pintype "bidirectional"))
      (node (ref "U3") (pin "3") (pinfunction "SQW/~{INT}_3") (pintype "output"))
    )
    (net (code "17") (name "IO{slash}BOOT") (class "Default")
      (node (ref "BOOT_BUTTON") (pin "3") (pinfunction "3_3") (pintype "passive"))
      (node (ref "BOOT_BUTTON") (pin "4") (pinfunction "4_4") (pintype "passive"))
      (node (ref "C6") (pin "1") (pinfunction "1_1") (pintype "passive"))
      (node (ref "R_BOOT") (pin "2") (pinfunction "2_2") (pintype "passive"))
      (node (ref "U2") (pin "15") (pinfunction "IO9_15") (pintype "bidirectional"))
    )
    (net (code "18") (name "IO{slash}CHANGE") (class "Default")
      (node (ref "C10") (pin "1") (pinfunction "1_1") (pintype "passive"))
      (node (ref "CHANGE_BUTTON") (pin "3") (pinfunction "3_3") (pintype "passive"))
      (node (ref "CHANGE_BUTTON") (pin "4") (pinfunction "4_4") (pintype "passive"))
      (node (ref "R_CHANGE") (pin "2") (pinfunction "2_2") (pintype "passive"))
      (node (ref "U2") (pin "23") (pinfunction "IO15_23") (pintype "bidirectional"))
    )
    (net (code "19") (name "MISO") (class "Default")
      (node (ref "D12") (pin "2") (pinfunction "2_2") (pintype "passive"))
      (node (ref "J4") (pin "P7") (pinfunction "DAT0_P7") (pintype "bidirectional"))
      (node (ref "MISO_TP6") (pin "TP") (pinfunction "TP_TP") (pintype "input"))
      (node (ref "R8") (pin "1") (pinfunction "1_1") (pintype "passive"))
      (node (ref "U2") (pin "27") (pinfunction "IO2_27") (pintype "bidirectional"))
      (node (ref "U5") (pin "2") (pinfunction "DO(IO1)_2") (pintype "bidirectional"))
    )
    (net (code "20") (name "MOSI") (class "Default")
      (node (ref "D11") (pin "2") (pinfunction "2_2") (pintype "passive"))
      (node (ref "J1") (pin "14") (pinfunction "14_14") (pintype "bidirectional"))
      (node (ref "J4") (pin "P3") (pinfunction "CMD_P3") (pintype "bidirectional"))
      (node (ref "MOSI_TP7") (pin "TP") (pinfunction "TP_TP") (pintype "input"))
      (node (ref "R7") (pin "1") (pinfunction "1_1") (pintype "passive"))
      (node (ref "U2") (pin "7") (pinfunction "IO7_7") (pintype "bidirectional"))
      (node (ref "U5") (pin "5") (pinfunction "DI(IO0)_5") (pintype "bidirectional"))
    )
    (net (code "21") (name "Net-(CHG_LED-PadC)") (class "Default")
      (node (ref "CHG_LED") (pin "C") (pinfunction "C_C") (pintype "passive"))
      (node (ref "R1_BAT") (pin "2") (pinfunction "2_2") (pintype "passive"))
    )
    (net (code "22") (name "Net-(D2-CATHODE)") (class "Default")
      (node (ref "C1_BAT1") (pin "1") (pinfunction "1_1") (pintype "passive"))
      (node (ref "D2") (pin "1") (pinfunction "CATHODE_1") (pintype "bidirectional"))
      (node (ref "IC4") (pin "1") (pinfunction "VIN_1") (pintype "bidirectional"))
      (node (ref "IC4") (pin "3") (pinfunction "CE_3") (pintype "bidirectional"))
      (node (ref "Q1") (pin "2") (pinfunction "S_2") (pintype "bidirectional"))
    )
    (net (code "23") (name "Net-(D3-A)") (class "Default")
      (node (ref "C4") (pin "1") (pinfunction "1_1") (pintype "passive"))
      (node (ref "D3") (pin "2") (pinfunction "A_2") (pintype "bidirectional"))
      (node (ref "D4") (pin "1") (pinfunction "K_1") (pintype "bidirectional"))
    )
    (net (code "24") (name "Net-(D7-CATHODE)") (class "Default")
      (node (ref "D7") (pin "1") (pinfunction "CATHODE_1") (pintype "bidirectional"))
      (node (ref "R_CAPACITOR") (pin "1") (pinfunction "1_1") (pintype "passive"))
    )
    (net (code "25") (name "Net-(EPD_C1-Pad1)") (class "Default")
      (node (ref "EPD_C1") (pin "1") (pinfunction "1_1") (pintype "passive"))
      (node (ref "J1") (pin "4") (pinfunction "4_4") (pintype "bidirectional"))
    )
    (net (code "26") (name "Net-(EPD_C2-Pad1)") (class "Default")
      (node (ref "EPD_C2") (pin "1") (pinfunction "1_1") (pintype "passive"))
      (node (ref "J1") (pin "5") (pinfunction "5_5") (pintype "bidirectional"))
    )
    (net (code "27") (name "Net-(EPD_C6-Pad1)") (class "Default")
      (node (ref "EPD_C6") (pin "1") (pinfunction "1_1") (pintype "passive"))
      (node (ref "J1") (pin "18") (pinfunction "18_18") (pintype "bidirectional"))
    )
    (net (code "28") (name "Net-(EPD_C7-Pad1)") (class "Default")
      (node (ref "EPD_C7") (pin "1") (pinfunction "1_1") (pintype "passive"))
      (node (ref "J1") (pin "19") (pinfunction "19_19") (pintype "bidirectional"))
    )
    (net (code "29") (name "Net-(EPD_C8-Pad1)") (class "Default")
      (node (ref "EPD_C8") (pin "1") (pinfunction "1_1") (pintype "passive"))
      (node (ref "J1") (pin "20") (pinfunction "20_20") (pintype "bidirectional"))
    )
    (net (code "30") (name "Net-(EPD_C10-Pad1)") (class "Default")
      (node (ref "EPD_C10") (pin "1") (pinfunction "1_1") (pintype "passive"))
      (node (ref "J1") (pin "22") (pinfunction "22_22") (pintype "bidirectional"))
    )
    (net (code "31") (name "Net-(EPD_C12-Pad1)") (class "Default")
      (node (ref "EPD_C12") (pin "1") (pinfunction "1_1") (pintype "passive"))
      (node (ref "J1") (pin "24") (pinfunction "24_24") (pintype "bidirectional"))
    )
    (net (code "32") (name "Net-(IC1-CT)") (class "Default")
      (node (ref "C_DELAY") (pin "1") (pinfunction "1_1") (pintype "passive"))
      (node (ref "IC1") (pin "5") (pinfunction "CT_5") (pintype "bidirectional"))
    )
    (net (code "33") (name "Net-(J2-PadA5)") (class "Default")
      (node (ref "J2") (pin "A5") (pinfunction "A5_A5") (pintype "bidirectional"))
      (node (ref "R2-USB1") (pin "2") (pinfunction "2_2") (pintype "passive"))
    )
    (net (code "34") (name "Net-(J2-PadB5)") (class "Default")
      (node (ref "J2") (pin "B5") (pinfunction "B5_B5") (pintype "bidirectional"))
      (node (ref "R2-USB") (pin "1") (pinfunction "1_1") (pintype "passive"))
    )
    (net (code "35") (name "Net-(R10-Pad2)") (class "Default")
      (node (ref "R10") (pin "2") (pinfunction "2_2") (pintype "passive"))
      (node (ref "R5") (pin "2") (pinfunction "2_2") (pintype "passive"))
      (node (ref "R6") (pin "2") (pinfunction "2_2") (pintype "passive"))
      (node (ref "R7") (pin "2") (pinfunction "2_2") (pintype "passive"))
      (node (ref "R8") (pin "2") (pinfunction "2_2") (pintype "passive"))
      (node (ref "R9") (pin "2") (pinfunction "2_2") (pintype "passive"))
    )
    (net (code "36") (name "Net-(U1-PROG)") (class "Default")
      (node (ref "R2_BAT") (pin "2") (pinfunction "2_2") (pintype "passive"))
      (node (ref "U1") (pin "5") (pinfunction "PROG_5") (pintype "input"))
    )
    (net (code "37") (name "Net-(U1-STAT)") (class "Default")
      (node (ref "R1_BAT") (pin "1") (pinfunction "1_1") (pintype "passive"))
      (node (ref "U1") (pin "1") (pinfunction "STAT_1") (pintype "output"))
    )
    (net (code "38") (name "PREVGH") (class "Default")
      (node (ref "D5") (pin "1") (pinfunction "K_1") (pintype "bidirectional"))
      (node (ref "EPD_C9") (pin "1") (pinfunction "1_1") (pintype "passive"))
      (node (ref "J1") (pin "21") (pinfunction "21_21") (pintype "bidirectional"))
    )
    (net (code "39") (name "PREVGL") (class "Default")
      (node (ref "D4") (pin "2") (pinfunction "A_2") (pintype "bidirectional"))
      (node (ref "EPD_C11") (pin "1") (pinfunction "1_1") (pintype "passive"))
      (node (ref "J1") (pin "23") (pinfunction "23_23") (pintype "bidirectional"))
    )
    (net (code "40") (name "RESE") (class "Default")
      (node (ref "J1") (pin "3") (pinfunction "3_3") (pintype "bidirectional"))
      (node (ref "Q3") (pin "2") (pinfunction "S_2") (pintype "bidirectional"))
      (node (ref "R3") (pin "1") (pinfunction "1_1") (pintype "passive"))
    )
    (net (code "41") (name "RESE'") (class "Default")
      (node (ref "R2") (pin "2") (pinfunction "2_2") (pintype "passive"))
      (node (ref "R3") (pin "2") (pinfunction "2_2") (pintype "passive"))
      (node (ref "SJ1") (pin "2") (pinfunction "2_2") (pintype "passive"))
    )
    (net (code "42") (name "RESET") (class "Default")
      (node (ref "C5") (pin "1") (pinfunction "1_1") (pintype "passive"))
      (node (ref "IC1") (pin "1") (pinfunction "VOUT_1") (pintype "bidirectional"))
      (node (ref "RESET_BUTTON") (pin "3") (pinfunction "3_3") (pintype "passive"))
      (node (ref "RESET_BUTTON") (pin "4") (pinfunction "4_4") (pintype "passive"))
      (node (ref "R_RESET") (pin "2") (pinfunction "2_2") (pintype "passive"))
      (node (ref "U2") (pin "3") (pinfunction "EN_3") (pintype "input"))
    )
    (net (code "43") (name "RTC_RST") (class "Default")
      (node (ref "U2") (pin "16") (pinfunction "IO18_16") (pintype "bidirectional"))
      (node (ref "U3") (pin "4") (pinfunction "~{RST}_4") (pintype "input"))
    )
    (net (code "44") (name "RX") (class "Default")
      (node (ref "RX_TP2") (pin "TP") (pinfunction "TP_TP") (pintype "input"))
      (node (ref "U2") (pin "24") (pinfunction "RXD0/GPIO17_24") (pintype "bidirectional"))
    )
    (net (code "45") (name "SCK") (class "Default")
      (node (ref "D10") (pin "2") (pinfunction "2_2") (pintype "passive"))
      (node (ref "J1") (pin "13") (pinfunction "13_13") (pintype "bidirectional"))
      (node (ref "J4") (pin "P5") (pinfunction "CLK_P5") (pintype "bidirectional"))
      (node (ref "R6") (pin "1") (pinfunction "1_1") (pintype "passive"))
      (node (ref "SCK_TP8") (pin "TP") (pinfunction "TP_TP") (pintype "input"))
      (node (ref "U2") (pin "6") (pinfunction "IO6_6") (pintype "bidirectional"))
      (node (ref "U5") (pin "6") (pinfunction "CLK_6") (pintype "input"))
    )
    (net (code "46") (name "SCL") (class "Default")
      (node (ref "J3") (pin "4") (pinfunction "4_4") (pintype "passive"))
      (node (ref "R2-PINH") (pin "1") (pinfunction "1_1") (pintype "passive"))
      (node (ref "SENSOR2") (pin "4") (pinfunction "SCK_4") (pintype "input"))
      (node (ref "U2") (pin "20") (pinfunction "IO22_20") (pintype "bidirectional"))
      (node (ref "U3") (pin "16") (pinfunction "SCL_16") (pintype "input"))
      (node (ref "U4") (pin "7") (pinfunction "SCL_7") (pintype "input"))
    )
    (net (code "47") (name "SDA") (class "Default")
      (node (ref "J3") (pin "3") (pinfunction "3_3") (pintype "passive"))
      (node (ref "R1-PINH") (pin "1") (pinfunction "1_1") (pintype "passive"))
      (node (ref "SENSOR2") (pin "3") (pinfunction "SDI_3") (pintype "bidirectional"))
      (node (ref "U2") (pin "19") (pinfunction "IO21_19") (pintype "bidirectional"))
      (node (ref "U3") (pin "15") (pinfunction "SDA_15") (pintype "bidirectional"))
      (node (ref "U4") (pin "8") (pinfunction "SDA_8") (pintype "bidirectional"))
    )
    (net (code "48") (name "SRC") (class "Default")
      (node (ref "C4") (pin "2") (pinfunction "2_2") (pintype "passive"))
      (node (ref "D5") (pin "2") (pinfunction "A_2") (pintype "bidirectional"))
      (node (ref "L1") (pin "1") (pinfunction "1_1") (pintype "passive"))
      (node (ref "Q3") (pin "3") (pinfunction "D_3") (pintype "bidirectional"))
    )
    (net (code "49") (name "SS_SD") (class "Default")
      (node (ref "D8") (pin "2") (pinfunction "2_2") (pintype "passive"))
      (node (ref "J4") (pin "P2") (pinfunction "CD/DAT3_P2") (pintype "bidirectional"))
      (node (ref "R10") (pin "1") (pinfunction "1_1") (pintype "passive"))
      (node (ref "U2") (pin "4") (pinfunction "IO4_4") (pintype "bidirectional"))
    )
    (net (code "50") (name "TX") (class "Default")
      (node (ref "TX_TP1") (pin "TP") (pinfunction "TP_TP") (pintype "input"))
      (node (ref "U2") (pin "25") (pinfunction "TXD0/GPIO16_25") (pintype "bidirectional"))
    )
    (net (code "51") (name "USB_D+") (class "Default")
      (node (ref "D1") (pin "1") (pinfunction "I/O1_1_1") (pintype "bidirectional"))
      (node (ref "U2") (pin "14") (pinfunction "IO13_14") (pintype "bidirectional"))
    )
    (net (code "52") (name "USB_D-") (class "Default")
      (node (ref "D1") (pin "3") (pinfunction "I/O2_1_3") (pintype "bidirectional"))
      (node (ref "U2") (pin "13") (pinfunction "IO12_13") (pintype "bidirectional"))
    )
    (net (code "53") (name "VBAT") (class "Default")
      (node (ref "C2_BAT") (pin "1") (pinfunction "1_1") (pintype "passive"))
      (node (ref "Q1") (pin "3") (pinfunction "D_3") (pintype "bidirectional"))
      (node (ref "U1") (pin "3") (pinfunction "VBAT_3") (pintype "power_in"))
      (node (ref "U4") (pin "2") (pinfunction "CELL_2") (pintype "power_in"))
      (node (ref "U4") (pin "3") (pinfunction "VDD_3") (pintype "power_in"))
      (node (ref "VBAT_TP3") (pin "TP") (pinfunction "TP_TP") (pintype "input"))
    )
    (net (code "54") (name "VBUS") (class "Default")
      (node (ref "C1_BAT") (pin "1") (pinfunction "1_1") (pintype "passive"))
      (node (ref "C4_USB") (pin "1") (pinfunction "1_1") (pintype "passive"))
      (node (ref "C5_USB") (pin "1") (pinfunction "1_1") (pintype "passive"))
      (node (ref "CHG_LED") (pin "A") (pinfunction "A_A") (pintype "passive"))
      (node (ref "D1") (pin "5") (pinfunction "VBUS_5") (pintype "bidirectional"))
      (node (ref "D2") (pin "2") (pinfunction "ANODE_2") (pintype "bidirectional"))
      (node (ref "PFMF.050.1") (pin "2") (pinfunction "2_2") (pintype "passive"))
      (node (ref "Q1") (pin "1") (pinfunction "G_1") (pintype "bidirectional"))
      (node (ref "R1_PWRUSB") (pin "2") (pinfunction "2_2") (pintype "passive"))
      (node (ref "U1") (pin "4") (pinfunction "VIN_4") (pintype "power_in"))
      (node (ref "VBUS_TP14") (pin "TP") (pinfunction "TP_TP") (pintype "input"))
    )
    (net (code "55") (name "VRTC") (class "Default")
      (node (ref "C10_SUPERCAP") (pin "2") (pinfunction "2_2") (pintype "passive"))
      (node (ref "C8") (pin "1") (pinfunction "1_1") (pintype "passive"))
      (node (ref "R_CAPACITOR") (pin "2") (pinfunction "2_2") (pintype "passive"))
      (node (ref "U3") (pin "14") (pinfunction "VBAT_14") (pintype "power_in"))
    )
    (net (code "56") (name "VUSB") (class "Default")
      (node (ref "J2") (pin "A4") (pinfunction "A4_A4") (pintype "bidirectional"))
      (node (ref "J2") (pin "A9") (pinfunction "A9_A9") (pintype "bidirectional"))
      (node (ref "J2") (pin "B4") (pinfunction "B4_B4") (pintype "bidirectional"))
      (node (ref "J2") (pin "B9") (pinfunction "B9_B9") (pintype "bidirectional"))
      (node (ref "PFMF.050.1") (pin "1") (pinfunction "1_1") (pintype "passive"))
    )
    (net (code "57") (name "unconnected-(IC1-NC-Pad4)") (class "Default")
      (node (ref "IC1") (pin "4") (pinfunction "NC_4") (pintype "no_connect"))
    )
    (net (code "58") (name "unconnected-(IC4-NC-Pad4)") (class "Default")
      (node (ref "IC4") (pin "4") (pinfunction "NC_4") (pintype "no_connect"))
    )
    (net (code "59") (name "unconnected-(J1-Pad1)") (class "Default")
      (node (ref "J1") (pin "1") (pinfunction "1_1") (pintype "bidirectional"))
    )
    (net (code "60") (name "unconnected-(J1-Pad6)") (class "Default")
      (node (ref "J1") (pin "6") (pinfunction "6_6") (pintype "bidirectional"))
    )
    (net (code "61") (name "unconnected-(J1-Pad7)") (class "Default")
      (node (ref "J1") (pin "7") (pinfunction "7_7") (pintype "bidirectional"))
    )
    (net (code "62") (name "unconnected-(J2-PadA8)") (class "Default")
      (node (ref "J2") (pin "A8") (pinfunction "A8_A8") (pintype "bidirectional"))
    )
    (net (code "63") (name "unconnected-(J2-PadB8)") (class "Default")
      (node (ref "J2") (pin "B8") (pinfunction "B8_B8") (pintype "bidirectional"))
    )
    (net (code "64") (name "unconnected-(J4-DAT1-PadP8)") (class "Default")
      (node (ref "J4") (pin "P8") (pinfunction "DAT1_P8") (pintype "bidirectional"))
    )
    (net (code "65") (name "unconnected-(J4-DAT2-PadP1)") (class "Default")
      (node (ref "J4") (pin "P1") (pinfunction "DAT2_P1") (pintype "bidirectional"))
    )
    (net (code "66") (name "unconnected-(J4-DETECTION_1-PadS1)") (class "Default")
      (node (ref "J4") (pin "S1") (pinfunction "DETECTION_1_S1") (pintype "bidirectional"))
    )
    (net (code "67") (name "unconnected-(J4-DETECTION_2-PadS2)") (class "Default")
      (node (ref "J4") (pin "S2") (pinfunction "DETECTION_2_S2") (pintype "bidirectional"))
    )
    (net (code "68") (name "unconnected-(U2-NC-Pad22)") (class "Default")
      (node (ref "U2") (pin "22") (pinfunction "NC_22") (pintype "no_connect"))
    )
    (net (code "69") (name "unconnected-(U4-~{ALERT}-Pad5)") (class "Default")
      (node (ref "U4") (pin "5") (pinfunction "~{ALERT}_5") (pintype "output"))
    )
  )
)
